# POWERBANK.net
KiCad netlist of a schematic drawn in Altium Designer
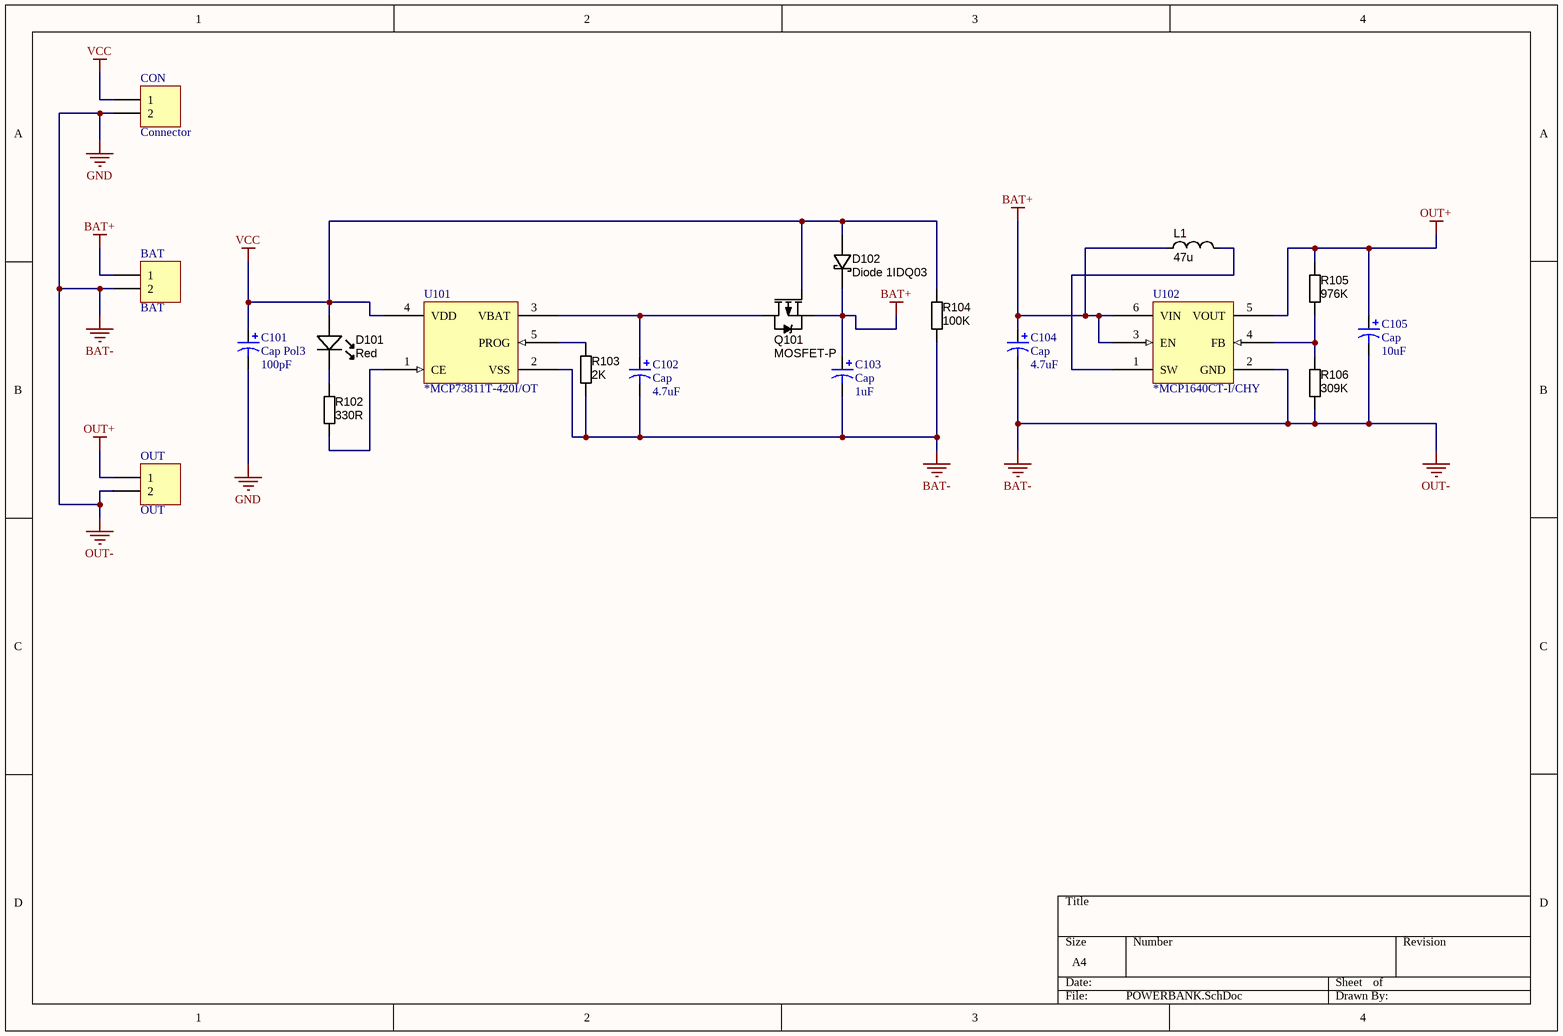
[diagram p0: POWERBANK.SchDoc]

(export (version "E")
  (design (tool "Eeschema 10.0.6"))
  (components
    (comp (ref "BAT")
      (value "BAT")
      (footprint "HDR1X2")
      (description "Header, 2-Pin")
      (fields (field (name "PUBLISHER") "Altium Limited"))
      (libsource (lib "Miscellaneous Connectors") (part "Header 2"))
    )
    (comp (ref "C101")
      (value "Cap Pol3")
      (footprint "CAPC1608X90N")
      (description "Polarized Capacitor (Surface Mount)")
      (fields (field (name "ALTIUM_VALUE") "100pF") (field (name "PUBLISHER") "Altium Limited"))
      (libsource (lib "Miscellaneous Devices") (part "Cap Pol3"))
    )
    (comp (ref "C102")
      (value "Cap")
      (footprint "CAPC1608X90N")
      (description "Polarized Capacitor (Surface Mount)")
      (fields (field (name "ALTIUM_VALUE") "4.7uF") (field (name "PUBLISHER") "Altium Limited"))
      (libsource (lib "Miscellaneous Devices") (part "Cap Pol3"))
    )
    (comp (ref "C103")
      (value "Cap")
      (footprint "CAPC1608X90N")
      (description "Polarized Capacitor (Surface Mount)")
      (fields (field (name "ALTIUM_VALUE") "1uF") (field (name "PUBLISHER") "Altium Limited"))
      (libsource (lib "Miscellaneous Devices") (part "Cap Pol3"))
    )
    (comp (ref "C104")
      (value "Cap")
      (footprint "CAPC1608X90N")
      (description "Polarized Capacitor (Surface Mount)")
      (fields (field (name "ALTIUM_VALUE") "4.7uF") (field (name "PUBLISHER") "Altium Limited"))
      (libsource (lib "Miscellaneous Devices") (part "Cap Pol3"))
    )
    (comp (ref "C105")
      (value "Cap")
      (footprint "CAPC1608X90N")
      (description "Polarized Capacitor (Surface Mount)")
      (fields (field (name "ALTIUM_VALUE") "10uF") (field (name "PUBLISHER") "Altium Limited"))
      (libsource (lib "Miscellaneous Devices") (part "Cap Pol3"))
    )
    (comp (ref "CON")
      (value "Connector")
      (footprint "HDR1X2")
      (description "Header, 2-Pin")
      (fields (field (name "PUBLISHER") "Altium Limited"))
      (libsource (lib "Miscellaneous Connectors") (part "Header 2"))
    )
    (comp (ref "D101")
      (value "~")
      (footprint "LED-0805-K")
      (description "LED, 0805 SMD, Green")
      (fields (field (name "COLOR") "Red"))
      (libsource (lib "PBL - Light Sources") (part "LED_SMD_Green_0805_6mcd"))
    )
    (comp (ref "D102")
      (value "DIODE_SCHOTTKY_10MQ100NPBF")
      (footprint "DO-214AC")
      (description "Diode Schottky SMD 100V 2A SMA")
      (fields (field (name "RATINGS") "Diode 1IDQ03"))
      (libsource (lib "PBL - Diodes") (part "DIODE_SCHOTTKY_10MQ100NPBF"))
    )
    (comp (ref "L1")
      (value "47u")
      (footprint "INDM2520X190N")
      (description "Inductor SMD chip 47nH 1008")
      (fields (field (name "TOLERANCE") "±5%"))
      (libsource (lib "PBL - Inductors") (part "INDC_47n_1008_1A"))
    )
    (comp (ref "OUT")
      (value "OUT")
      (footprint "HDR1X2")
      (description "Header, 2-Pin")
      (fields (field (name "PUBLISHER") "Altium Limited"))
      (libsource (lib "Miscellaneous Connectors") (part "Header 2"))
    )
    (comp (ref "Q101")
      (value "MOSFET-P")
      (footprint "SOT23-3")
      (description "MOSFET SMD P-CH 50V 130mA SOT23-3")
      (libsource (lib "PBL - Transistors") (part "MOSFET_BSS84"))
    )
    (comp (ref "R102")
      (value "330R")
      (footprint "RESC2012N_ZERO")
      (description "Resistor SMD chip 0.0 Ohm 0.125W 0805")
      (fields (field (name "Comment") "Jumper"))
      (libsource (lib "PBL - Resistors") (part "RES_0R_0805"))
    )
    (comp (ref "R103")
      (value "2K")
      (footprint "RESC2012N_ZERO")
      (description "Resistor SMD chip 0.0 Ohm 0.125W 0805")
      (fields (field (name "Comment") "Jumper"))
      (libsource (lib "PBL - Resistors") (part "RES_0R_0805"))
    )
    (comp (ref "R104")
      (value "100K")
      (footprint "RESC2012N_ZERO")
      (description "Resistor SMD chip 0.0 Ohm 0.125W 0805")
      (fields (field (name "Comment") "Jumper"))
      (libsource (lib "PBL - Resistors") (part "RES_0R_0805"))
    )
    (comp (ref "R105")
      (value "976K")
      (footprint "RESC2012N_ZERO")
      (description "Resistor SMD chip 0.0 Ohm 0.125W 0805")
      (fields (field (name "Comment") "Jumper"))
      (libsource (lib "PBL - Resistors") (part "RES_0R_0805"))
    )
    (comp (ref "R106")
      (value "309K")
      (footprint "RESC2012N_ZERO")
      (description "Resistor SMD chip 0.0 Ohm 0.125W 0805")
      (fields (field (name "Comment") "Jumper"))
      (libsource (lib "PBL - Resistors") (part "RES_0R_0805"))
    )
    (comp (ref "U101")
      (value "*MCP73811T-420I/OT")
      (footprint "SOT23-5")
      (description "MCP73811T-420I/OT")
      (libsource (lib "MCP73811T_420IOT") (part "MCP73811T-420I/OT"))
    )
    (comp (ref "U102")
      (value "*MCP1640CT-I/CHY")
      (footprint "SOT23-6")
      (libsource (lib "MCP1640CT_ICHY") (part "MCP1640CT-I/CHY"))
    )
  )
  (nets
    (net (code "1") (name "BAT+") (class "Default")
      (node (ref "BAT") (pin "1") (pinfunction "1_1") (pintype "passive"))
      (node (ref "C103") (pin "1") (pinfunction "1_1") (pintype "passive"))
      (node (ref "C104") (pin "1") (pinfunction "1_1") (pintype "passive"))
      (node (ref "D102") (pin "K") (pinfunction "K_K") (pintype "passive"))
      (node (ref "L1") (pin "1") (pinfunction "1_1") (pintype "passive"))
      (node (ref "Q101") (pin "2") (pinfunction "S_2") (pintype "passive"))
      (node (ref "U102") (pin "3") (pinfunction "EN_3") (pintype "input"))
      (node (ref "U102") (pin "6") (pinfunction "VIN_6") (pintype "power_in"))
    )
    (net (code "2") (name "BAT-") (class "Default")
      (node (ref "BAT") (pin "2") (pinfunction "2_2") (pintype "passive"))
      (node (ref "C101") (pin "2") (pinfunction "2_2") (pintype "passive"))
      (node (ref "C102") (pin "2") (pinfunction "2_2") (pintype "passive"))
      (node (ref "C103") (pin "2") (pinfunction "2_2") (pintype "passive"))
      (node (ref "C104") (pin "2") (pinfunction "2_2") (pintype "passive"))
      (node (ref "C105") (pin "2") (pinfunction "2_2") (pintype "passive"))
      (node (ref "CON") (pin "2") (pinfunction "2_2") (pintype "passive"))
      (node (ref "OUT") (pin "2") (pinfunction "2_2") (pintype "passive"))
      (node (ref "R103") (pin "2") (pinfunction "2_2") (pintype "passive"))
      (node (ref "R104") (pin "2") (pinfunction "2_2") (pintype "passive"))
      (node (ref "R106") (pin "2") (pinfunction "2_2") (pintype "passive"))
      (node (ref "U101") (pin "2") (pinfunction "VSS_2") (pintype "passive"))
      (node (ref "U102") (pin "2") (pinfunction "GND_2") (pintype "power_in"))
    )
    (net (code "3") (name "Net-(D101-PadK)") (class "Default")
      (node (ref "D101") (pin "K") (pinfunction "K_K") (pintype "passive"))
      (node (ref "R102") (pin "1") (pinfunction "1_1") (pintype "passive"))
    )
    (net (code "4") (name "Net-(Q101-D)") (class "Default")
      (node (ref "C102") (pin "1") (pinfunction "1_1") (pintype "passive"))
      (node (ref "Q101") (pin "3") (pinfunction "D_3") (pintype "passive"))
      (node (ref "U101") (pin "3") (pinfunction "VBAT_3") (pintype "passive"))
    )
    (net (code "5") (name "Net-(U101-CE)") (class "Default")
      (node (ref "R102") (pin "2") (pinfunction "2_2") (pintype "passive"))
      (node (ref "U101") (pin "1") (pinfunction "CE_1") (pintype "input"))
    )
    (net (code "6") (name "Net-(U101-PROG)") (class "Default")
      (node (ref "R103") (pin "1") (pinfunction "1_1") (pintype "passive"))
      (node (ref "U101") (pin "5") (pinfunction "PROG_5") (pintype "input"))
    )
    (net (code "7") (name "Net-(U102-FB)") (class "Default")
      (node (ref "R105") (pin "2") (pinfunction "2_2") (pintype "passive"))
      (node (ref "R106") (pin "1") (pinfunction "1_1") (pintype "passive"))
      (node (ref "U102") (pin "4") (pinfunction "FB_4") (pintype "input"))
    )
    (net (code "8") (name "Net-(U102-SW)") (class "Default")
      (node (ref "L1") (pin "2") (pinfunction "2_2") (pintype "passive"))
      (node (ref "U102") (pin "1") (pinfunction "SW_1") (pintype "passive"))
    )
    (net (code "9") (name "OUT+") (class "Default")
      (node (ref "C105") (pin "1") (pinfunction "1_1") (pintype "passive"))
      (node (ref "OUT") (pin "1") (pinfunction "1_1") (pintype "passive"))
      (node (ref "R105") (pin "1") (pinfunction "1_1") (pintype "passive"))
      (node (ref "U102") (pin "5") (pinfunction "VOUT_5") (pintype "power_in"))
    )
    (net (code "10") (name "VCC") (class "Default")
      (node (ref "C101") (pin "1") (pinfunction "1_1") (pintype "passive"))
      (node (ref "CON") (pin "1") (pinfunction "1_1") (pintype "passive"))
      (node (ref "D101") (pin "A") (pinfunction "A_A") (pintype "passive"))
      (node (ref "D102") (pin "A") (pinfunction "A_A") (pintype "passive"))
      (node (ref "Q101") (pin "1") (pinfunction "G_1") (pintype "passive"))
      (node (ref "R104") (pin "1") (pinfunction "1_1") (pintype "passive"))
      (node (ref "U101") (pin "4") (pinfunction "VDD_4") (pintype "passive"))
    )
  )
)
